# PPGGlove.net
KiCad netlist of a schematic drawn in EAGLE
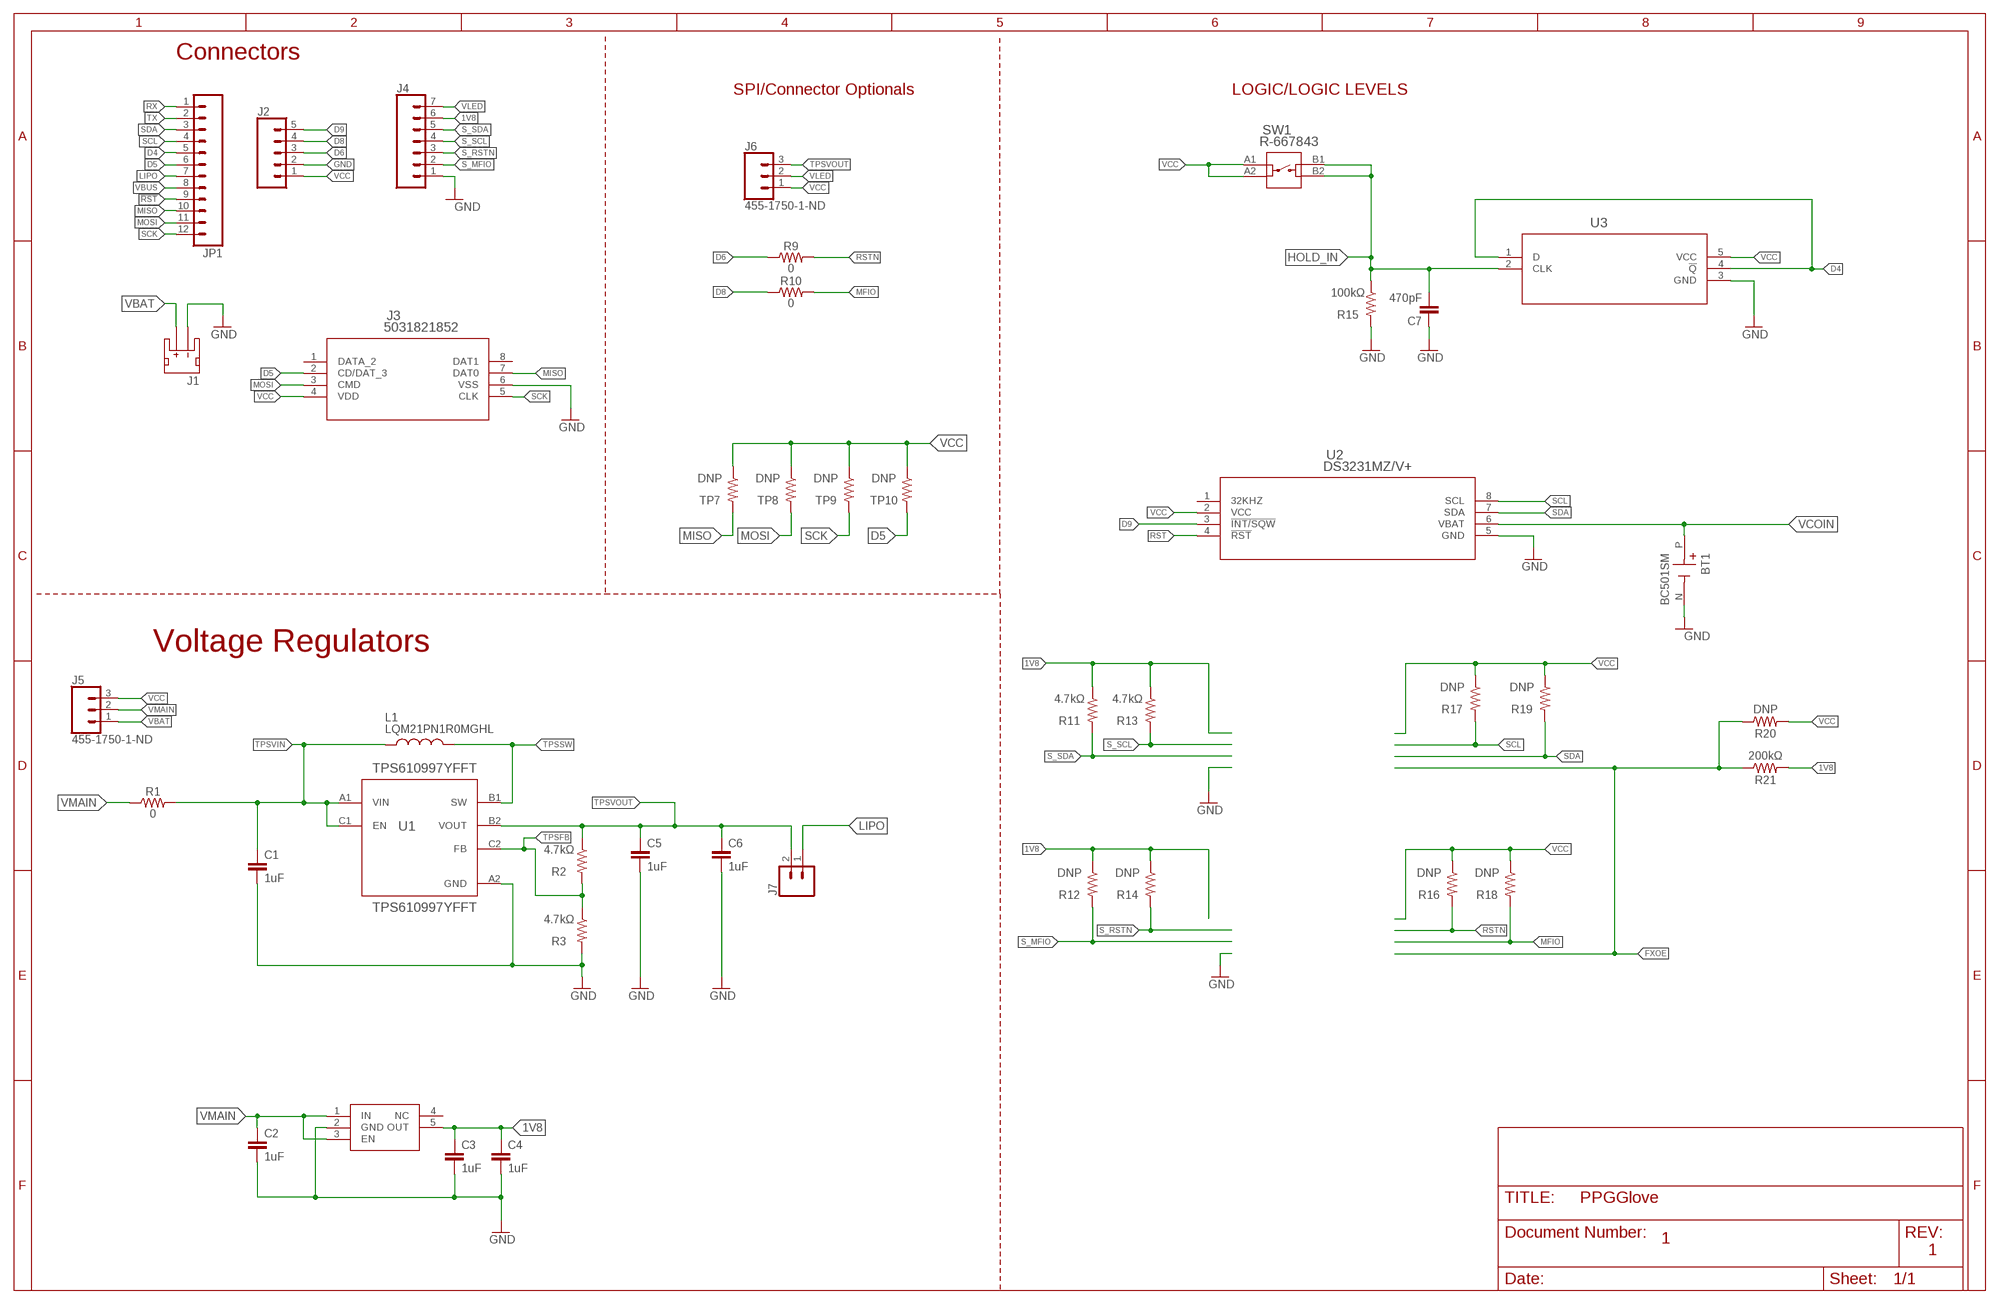
[diagram p0: schematic, sheet 1]

(export (version "E")
  (design (tool "Eeschema 10.0.6"))
  (components
    (comp (ref "BT1")
      (value "BC501SM")
      (footprint "eagle-import:BAT_BC501SM")
      (fields (field (name "DIGI-KEY_PART_NUMBER") "BC501SM-ND") (field (name "MF") "MPD"))
      (libsource (lib "eagle-import") (part "BC501SM"))
    )
    (comp (ref "C1")
      (value "1uF")
      (footprint "eagle-import:0805")
      (libsource (lib "eagle-import") (part "CAP-0805"))
    )
    (comp (ref "C2")
      (value "1uF")
      (footprint "eagle-import:0805")
      (libsource (lib "eagle-import") (part "CAP-0805"))
    )
    (comp (ref "C3")
      (value "1uF")
      (footprint "eagle-import:0805")
      (libsource (lib "eagle-import") (part "CAP-0805"))
    )
    (comp (ref "C4")
      (value "1uF")
      (footprint "eagle-import:0805")
      (libsource (lib "eagle-import") (part "CAP-0805"))
    )
    (comp (ref "C5")
      (value "1uF")
      (footprint "eagle-import:0805")
      (libsource (lib "eagle-import") (part "CAP-0805"))
    )
    (comp (ref "C6")
      (value "1uF")
      (footprint "eagle-import:0805")
      (libsource (lib "eagle-import") (part "CAP-0805"))
    )
    (comp (ref "C7")
      (value "470pF")
      (footprint "eagle-import:0805")
      (libsource (lib "eagle-import") (part "CAP-0805"))
    )
    (comp (ref "IC1")
      (value "TPS7A0318DBVR")
      (footprint "eagle-import:SOT95P280X145-5N")
      (fields (field (name "MOUSER_PART_NUMBER") "595-TPS7A0318DBVR"))
      (libsource (lib "eagle-import") (part "TPS7A0318DBVR"))
    )
    (comp (ref "J1")
      (value "JST_2MM_MALE")
      (footprint "eagle-import:JST-2-SMD")
      (libsource (lib "eagle-import") (part "JST_2MM_MALE"))
    )
    (comp (ref "J2")
      (value "CONN_05")
      (footprint "eagle-import:1X05")
      (libsource (lib "eagle-import") (part "CONN_05"))
    )
    (comp (ref "J3")
      (value "5031821852")
      (footprint "eagle-import:503182-1852_MOL")
      (fields (field (name "COPYRIGHT") "Copyright (C) 2022 Ultra Librarian. All rights reserved."))
      (libsource (lib "eagle-import") (part "5031821852"))
    )
    (comp (ref "J4")
      (value "CONN_07")
      (footprint "eagle-import:1X07")
      (libsource (lib "eagle-import") (part "CONN_07"))
    )
    (comp (ref "J5")
      (value "455-1750-1-ND")
      (footprint "eagle-import:1X03")
      (libsource (lib "eagle-import") (part "CONN_03"))
    )
    (comp (ref "J6")
      (value "455-1750-1-ND")
      (footprint "eagle-import:1X03")
      (libsource (lib "eagle-import") (part "CONN_03"))
    )
    (comp (ref "J7")
      (value "CONN_02")
      (footprint "eagle-import:1X02")
      (libsource (lib "eagle-import") (part "CONN_02"))
    )
    (comp (ref "JP1")
      (value "M12PTH")
      (footprint "eagle-import:1X12")
      (libsource (lib "eagle-import") (part "M12PTH"))
    )
    (comp (ref "L1")
      (value "LQM21PN1R0MGHL")
      (footprint "eagle-import:INDC2012X100N")
      (fields (field (name "DIGI-KEY_PART_NUMBER") "490-9572-2-ND") (field (name "MF") "Murata"))
      (libsource (lib "eagle-import") (part "LQM21PN1R0MGHL"))
    )
    (comp (ref "R1")
      (value "0")
      (footprint "eagle-import:0805")
      (libsource (lib "eagle-import") (part "RESISTOR0805"))
    )
    (comp (ref "R2")
      (value "4.7kΩ")
      (footprint "eagle-import:0805")
      (libsource (lib "eagle-import") (part "RESISTOR0805"))
    )
    (comp (ref "R3")
      (value "4.7kΩ")
      (footprint "eagle-import:0805")
      (libsource (lib "eagle-import") (part "RESISTOR0805"))
    )
    (comp (ref "R9")
      (value "0")
      (footprint "eagle-import:0805")
      (libsource (lib "eagle-import") (part "RESISTOR0805"))
    )
    (comp (ref "R10")
      (value "0")
      (footprint "eagle-import:0805")
      (libsource (lib "eagle-import") (part "RESISTOR0805"))
    )
    (comp (ref "R11")
      (value "4.7kΩ")
      (footprint "eagle-import:0805")
      (libsource (lib "eagle-import") (part "RESISTOR0805"))
    )
    (comp (ref "R12")
      (value "DNP")
      (footprint "eagle-import:0805")
      (libsource (lib "eagle-import") (part "RESISTOR0805"))
    )
    (comp (ref "R13")
      (value "4.7kΩ")
      (footprint "eagle-import:0805")
      (libsource (lib "eagle-import") (part "RESISTOR0805"))
    )
    (comp (ref "R14")
      (value "DNP")
      (footprint "eagle-import:0805")
      (libsource (lib "eagle-import") (part "RESISTOR0805"))
    )
    (comp (ref "R15")
      (value "100kΩ")
      (footprint "eagle-import:0805")
      (libsource (lib "eagle-import") (part "RESISTOR0805"))
    )
    (comp (ref "R16")
      (value "DNP")
      (footprint "eagle-import:0805")
      (libsource (lib "eagle-import") (part "RESISTOR0805"))
    )
    (comp (ref "R17")
      (value "DNP")
      (footprint "eagle-import:0805")
      (libsource (lib "eagle-import") (part "RESISTOR0805"))
    )
    (comp (ref "R18")
      (value "DNP")
      (footprint "eagle-import:0805")
      (libsource (lib "eagle-import") (part "RESISTOR0805"))
    )
    (comp (ref "R19")
      (value "DNP")
      (footprint "eagle-import:0805")
      (libsource (lib "eagle-import") (part "RESISTOR0805"))
    )
    (comp (ref "R20")
      (value "DNP")
      (footprint "eagle-import:0805")
      (libsource (lib "eagle-import") (part "RESISTOR0805"))
    )
    (comp (ref "R21")
      (value "200kΩ")
      (footprint "eagle-import:0805")
      (libsource (lib "eagle-import") (part "RESISTOR0805"))
    )
    (comp (ref "SW1")
      (value "R-667843")
      (footprint "eagle-import:R-667843_MIT")
      (fields (field (name "COPYRIGHT") "Copyright (C) 2022 Ultra Librarian. All rights reserved."))
      (libsource (lib "eagle-import") (part "R-667843"))
    )
    (comp (ref "TP7")
      (value "DNP")
      (footprint "eagle-import:0805")
      (libsource (lib "eagle-import") (part "RESISTOR0805"))
    )
    (comp (ref "TP8")
      (value "DNP")
      (footprint "eagle-import:0805")
      (libsource (lib "eagle-import") (part "RESISTOR0805"))
    )
    (comp (ref "TP9")
      (value "DNP")
      (footprint "eagle-import:0805")
      (libsource (lib "eagle-import") (part "RESISTOR0805"))
    )
    (comp (ref "TP10")
      (value "DNP")
      (footprint "eagle-import:0805")
      (libsource (lib "eagle-import") (part "RESISTOR0805"))
    )
    (comp (ref "U1")
      (value "TPS610997YFFT")
      (footprint "eagle-import:YFF0006AFAD")
      (fields (field (name "COPYRIGHT") "Copyright (C) 2022 Ultra Librarian. All rights reserved."))
      (libsource (lib "eagle-import") (part "TPS610997YFFT"))
    )
    (comp (ref "U2")
      (value "DS3231MZ/V+")
      (footprint "eagle-import:21-0041B_8_MXM")
      (fields (field (name "COPYRIGHT") "Copyright (C) 2022 Ultra Librarian. All rights reserved."))
      (libsource (lib "eagle-import") (part "DS3231MZ/V+"))
    )
    (comp (ref "U5")
      (value "U3")
      (footprint "eagle-import:DBV5")
      (fields
        (field (name "MANUFACTURER_PART_NUMBER") "SN74AUP1G80DBVR")
        (field (name "COPYRIGHT") "Copyright (C) 2022 Ultra Librarian. All rights reserved.")
      )
      (libsource (lib "eagle-import") (part "SN74AUP1G80DBVR"))
    )
  )
  (nets
    (net (code "1") (name "/~{RST}") (class "Default")
      (node (ref "JP1") (pin "9") (pinfunction "9_9") (pintype "passive"))
    )
    (net (code "2") (name "1V8") (class "Default")
      (node (ref "C3") (pin "1") (pinfunction "1_1") (pintype "passive"))
      (node (ref "C4") (pin "1") (pinfunction "1_1") (pintype "passive"))
      (node (ref "IC1") (pin "5") (pinfunction "OUT_5") (pintype "bidirectional"))
      (node (ref "J4") (pin "6") (pinfunction "6_6") (pintype "passive"))
      (node (ref "R11") (pin "1") (pinfunction "1_1") (pintype "passive"))
      (node (ref "R12") (pin "1") (pinfunction "1_1") (pintype "passive"))
      (node (ref "R13") (pin "1") (pinfunction "1_1") (pintype "passive"))
      (node (ref "R14") (pin "1") (pinfunction "1_1") (pintype "passive"))
      (node (ref "R21") (pin "2") (pinfunction "2_2") (pintype "passive"))
    )
    (net (code "3") (name "D4") (class "Default")
      (node (ref "JP1") (pin "5") (pinfunction "5_5") (pintype "passive"))
      (node (ref "U5") (pin "1") (pinfunction "D_1") (pintype "input"))
      (node (ref "U5") (pin "4") (pinfunction "~{Q}_4") (pintype "output"))
    )
    (net (code "4") (name "D5") (class "Default")
      (node (ref "J3") (pin "2") (pinfunction "CD/DAT_3_2") (pintype "bidirectional"))
      (node (ref "JP1") (pin "6") (pinfunction "6_6") (pintype "passive"))
      (node (ref "TP10") (pin "2") (pinfunction "2_2") (pintype "passive"))
    )
    (net (code "5") (name "D6") (class "Default")
      (node (ref "J2") (pin "3") (pinfunction "3_3") (pintype "passive"))
      (node (ref "R9") (pin "1") (pinfunction "1_1") (pintype "passive"))
    )
    (net (code "6") (name "D8") (class "Default")
      (node (ref "J2") (pin "4") (pinfunction "4_4") (pintype "passive"))
      (node (ref "R10") (pin "1") (pinfunction "1_1") (pintype "passive"))
    )
    (net (code "7") (name "D9") (class "Default")
      (node (ref "J2") (pin "5") (pinfunction "5_5") (pintype "passive"))
      (node (ref "U2") (pin "3") (pinfunction "~{INT/SQW}_3") (pintype "bidirectional"))
    )
    (net (code "8") (name "FXOE") (class "Default")
      (node (ref "R20") (pin "1") (pinfunction "1_1") (pintype "passive"))
      (node (ref "R21") (pin "1") (pinfunction "1_1") (pintype "passive"))
    )
    (net (code "9") (name "GND") (class "Default")
      (node (ref "BT1") (pin "N") (pinfunction "-_N") (pintype "passive"))
      (node (ref "C1") (pin "2") (pinfunction "2_2") (pintype "passive"))
      (node (ref "C2") (pin "2") (pinfunction "2_2") (pintype "passive"))
      (node (ref "C3") (pin "2") (pinfunction "2_2") (pintype "passive"))
      (node (ref "C4") (pin "2") (pinfunction "2_2") (pintype "passive"))
      (node (ref "C5") (pin "2") (pinfunction "2_2") (pintype "passive"))
      (node (ref "C6") (pin "2") (pinfunction "2_2") (pintype "passive"))
      (node (ref "C7") (pin "1") (pinfunction "1_1") (pintype "passive"))
      (node (ref "IC1") (pin "2") (pinfunction "GND_2") (pintype "bidirectional"))
      (node (ref "J1") (pin "1") (pinfunction "-_1") (pintype "bidirectional"))
      (node (ref "J2") (pin "2") (pinfunction "2_2") (pintype "passive"))
      (node (ref "J3") (pin "6") (pinfunction "VSS_6") (pintype "passive"))
      (node (ref "J4") (pin "1") (pinfunction "1_1") (pintype "passive"))
      (node (ref "R15") (pin "2") (pinfunction "2_2") (pintype "passive"))
      (node (ref "R3") (pin "2") (pinfunction "2_2") (pintype "passive"))
      (node (ref "U1") (pin "A2") (pinfunction "GND_A2") (pintype "power_in"))
      (node (ref "U2") (pin "5") (pinfunction "GND_5") (pintype "power_in"))
      (node (ref "U5") (pin "3") (pinfunction "GND_3") (pintype "power_in"))
    )
    (net (code "10") (name "HOLD_IN") (class "Default")
      (node (ref "C7") (pin "2") (pinfunction "2_2") (pintype "passive"))
      (node (ref "R15") (pin "1") (pinfunction "1_1") (pintype "passive"))
      (node (ref "SW1") (pin "B1") (pinfunction "B1_B1") (pintype "passive"))
      (node (ref "SW1") (pin "B2") (pinfunction "B2_B2") (pintype "passive"))
      (node (ref "U5") (pin "2") (pinfunction "CLK_2") (pintype "input"))
    )
    (net (code "11") (name "LIPO") (class "Default")
      (node (ref "J7") (pin "1") (pinfunction "1_1") (pintype "passive"))
      (node (ref "JP1") (pin "7") (pinfunction "7_7") (pintype "passive"))
    )
    (net (code "12") (name "MFIO") (class "Default")
      (node (ref "R10") (pin "2") (pinfunction "2_2") (pintype "passive"))
      (node (ref "R18") (pin "2") (pinfunction "2_2") (pintype "passive"))
    )
    (net (code "13") (name "MISO") (class "Default")
      (node (ref "J3") (pin "7") (pinfunction "DAT0_7") (pintype "bidirectional"))
      (node (ref "JP1") (pin "10") (pinfunction "10_10") (pintype "passive"))
      (node (ref "TP7") (pin "2") (pinfunction "2_2") (pintype "passive"))
    )
    (net (code "14") (name "MOSI") (class "Default")
      (node (ref "J3") (pin "3") (pinfunction "CMD_3") (pintype "passive"))
      (node (ref "JP1") (pin "11") (pinfunction "11_11") (pintype "passive"))
      (node (ref "TP8") (pin "2") (pinfunction "2_2") (pintype "passive"))
    )
    (net (code "15") (name "RST") (class "Default")
      (node (ref "U2") (pin "4") (pinfunction "~{RST}_4") (pintype "passive"))
    )
    (net (code "16") (name "RSTN") (class "Default")
      (node (ref "R16") (pin "2") (pinfunction "2_2") (pintype "passive"))
      (node (ref "R9") (pin "2") (pinfunction "2_2") (pintype "passive"))
    )
    (net (code "17") (name "RX") (class "Default")
      (node (ref "JP1") (pin "1") (pinfunction "1_1") (pintype "passive"))
    )
    (net (code "18") (name "SCK") (class "Default")
      (node (ref "J3") (pin "5") (pinfunction "CLK_5") (pintype "passive"))
      (node (ref "JP1") (pin "12") (pinfunction "12_12") (pintype "passive"))
      (node (ref "TP9") (pin "2") (pinfunction "2_2") (pintype "passive"))
    )
    (net (code "19") (name "SCL") (class "Default")
      (node (ref "JP1") (pin "4") (pinfunction "4_4") (pintype "passive"))
      (node (ref "R17") (pin "2") (pinfunction "2_2") (pintype "passive"))
      (node (ref "U2") (pin "8") (pinfunction "SCL_8") (pintype "input"))
    )
    (net (code "20") (name "SDA") (class "Default")
      (node (ref "JP1") (pin "3") (pinfunction "3_3") (pintype "passive"))
      (node (ref "R19") (pin "2") (pinfunction "2_2") (pintype "passive"))
      (node (ref "U2") (pin "7") (pinfunction "SDA_7") (pintype "passive"))
    )
    (net (code "21") (name "S_MFIO") (class "Default")
      (node (ref "J4") (pin "2") (pinfunction "2_2") (pintype "passive"))
      (node (ref "R12") (pin "2") (pinfunction "2_2") (pintype "passive"))
    )
    (net (code "22") (name "S_RSTN") (class "Default")
      (node (ref "J4") (pin "3") (pinfunction "3_3") (pintype "passive"))
      (node (ref "R14") (pin "2") (pinfunction "2_2") (pintype "passive"))
    )
    (net (code "23") (name "S_SCL") (class "Default")
      (node (ref "J4") (pin "4") (pinfunction "4_4") (pintype "passive"))
      (node (ref "R13") (pin "2") (pinfunction "2_2") (pintype "passive"))
    )
    (net (code "24") (name "S_SDA") (class "Default")
      (node (ref "J4") (pin "5") (pinfunction "5_5") (pintype "passive"))
      (node (ref "R11") (pin "2") (pinfunction "2_2") (pintype "passive"))
    )
    (net (code "25") (name "TPSFB") (class "Default")
      (node (ref "R2") (pin "2") (pinfunction "2_2") (pintype "passive"))
      (node (ref "R3") (pin "1") (pinfunction "1_1") (pintype "passive"))
      (node (ref "U1") (pin "C2") (pinfunction "FB_C2") (pintype "input"))
    )
    (net (code "26") (name "TPSSW") (class "Default")
      (node (ref "L1") (pin "2") (pinfunction "2_2") (pintype "passive"))
      (node (ref "U1") (pin "B1") (pinfunction "SW_B1") (pintype "power_in"))
    )
    (net (code "27") (name "TPSVIN") (class "Default")
      (node (ref "C1") (pin "1") (pinfunction "1_1") (pintype "passive"))
      (node (ref "L1") (pin "1") (pinfunction "1_1") (pintype "passive"))
      (node (ref "R1") (pin "2") (pinfunction "2_2") (pintype "passive"))
      (node (ref "U1") (pin "A1") (pinfunction "VIN_A1") (pintype "power_in"))
      (node (ref "U1") (pin "C1") (pinfunction "EN_C1") (pintype "input"))
    )
    (net (code "28") (name "TPSVOUT") (class "Default")
      (node (ref "C5") (pin "1") (pinfunction "1_1") (pintype "passive"))
      (node (ref "C6") (pin "1") (pinfunction "1_1") (pintype "passive"))
      (node (ref "J6") (pin "3") (pinfunction "3_3") (pintype "passive"))
      (node (ref "J7") (pin "2") (pinfunction "2_2") (pintype "passive"))
      (node (ref "R2") (pin "1") (pinfunction "1_1") (pintype "passive"))
      (node (ref "U1") (pin "B2") (pinfunction "VOUT_B2") (pintype "power_in"))
    )
    (net (code "29") (name "TX") (class "Default")
      (node (ref "JP1") (pin "2") (pinfunction "2_2") (pintype "passive"))
    )
    (net (code "30") (name "VBAT") (class "Default")
      (node (ref "J1") (pin "2") (pinfunction "+_2") (pintype "bidirectional"))
      (node (ref "J5") (pin "1") (pinfunction "1_1") (pintype "passive"))
    )
    (net (code "31") (name "VBUS") (class "Default")
      (node (ref "JP1") (pin "8") (pinfunction "8_8") (pintype "passive"))
    )
    (net (code "32") (name "VCC") (class "Default")
      (node (ref "J2") (pin "1") (pinfunction "1_1") (pintype "passive"))
      (node (ref "J3") (pin "4") (pinfunction "VDD_4") (pintype "power_in"))
      (node (ref "J5") (pin "3") (pinfunction "3_3") (pintype "passive"))
      (node (ref "J6") (pin "1") (pinfunction "1_1") (pintype "passive"))
      (node (ref "R16") (pin "1") (pinfunction "1_1") (pintype "passive"))
      (node (ref "R17") (pin "1") (pinfunction "1_1") (pintype "passive"))
      (node (ref "R18") (pin "1") (pinfunction "1_1") (pintype "passive"))
      (node (ref "R19") (pin "1") (pinfunction "1_1") (pintype "passive"))
      (node (ref "R20") (pin "2") (pinfunction "2_2") (pintype "passive"))
      (node (ref "SW1") (pin "A1") (pinfunction "A1_A1") (pintype "passive"))
      (node (ref "SW1") (pin "A2") (pinfunction "A2_A2") (pintype "passive"))
      (node (ref "TP10") (pin "1") (pinfunction "1_1") (pintype "passive"))
      (node (ref "TP7") (pin "1") (pinfunction "1_1") (pintype "passive"))
      (node (ref "TP8") (pin "1") (pinfunction "1_1") (pintype "passive"))
      (node (ref "TP9") (pin "1") (pinfunction "1_1") (pintype "passive"))
      (node (ref "U2") (pin "2") (pinfunction "VCC_2") (pintype "power_in"))
      (node (ref "U5") (pin "5") (pinfunction "VCC_5") (pintype "power_in"))
    )
    (net (code "33") (name "VCOIN") (class "Default")
      (node (ref "BT1") (pin "P") (pinfunction "+_P") (pintype "passive"))
      (node (ref "U2") (pin "6") (pinfunction "VBAT_6") (pintype "power_in"))
    )
    (net (code "34") (name "VLED") (class "Default")
      (node (ref "J4") (pin "7") (pinfunction "7_7") (pintype "passive"))
      (node (ref "J6") (pin "2") (pinfunction "2_2") (pintype "passive"))
    )
    (net (code "35") (name "VMAIN") (class "Default")
      (node (ref "C2") (pin "1") (pinfunction "1_1") (pintype "passive"))
      (node (ref "IC1") (pin "1") (pinfunction "IN_1") (pintype "bidirectional"))
      (node (ref "IC1") (pin "3") (pinfunction "EN_3") (pintype "bidirectional"))
      (node (ref "J5") (pin "2") (pinfunction "2_2") (pintype "passive"))
      (node (ref "R1") (pin "1") (pinfunction "1_1") (pintype "passive"))
    )
    (net (code "36") (name "unconnected-(IC1-NC-Pad4)") (class "Default")
      (node (ref "IC1") (pin "4") (pinfunction "NC_4") (pintype "no_connect"))
    )
    (net (code "37") (name "unconnected-(J1-PAD1-PadNC1)") (class "Default")
      (node (ref "J1") (pin "NC1") (pinfunction "PAD1_NC1") (pintype "bidirectional"))
    )
    (net (code "38") (name "unconnected-(J1-PAD2-PadNC2)") (class "Default")
      (node (ref "J1") (pin "NC2") (pinfunction "PAD2_NC2") (pintype "bidirectional"))
    )
    (net (code "39") (name "unconnected-(J3-DAT1-Pad8)") (class "Default")
      (node (ref "J3") (pin "8") (pinfunction "DAT1_8") (pintype "no_connect"))
    )
    (net (code "40") (name "unconnected-(J3-DATA_2-Pad1)") (class "Default")
      (node (ref "J3") (pin "1") (pinfunction "DATA_2_1") (pintype "no_connect"))
    )
    (net (code "41") (name "unconnected-(U2-32KHZ-Pad1)") (class "Default")
      (node (ref "U2") (pin "1") (pinfunction "32KHZ_1") (pintype "no_connect"))
    )
  )
)
